# 00C-004.net
KiCad netlist of a schematic drawn in EAGLE
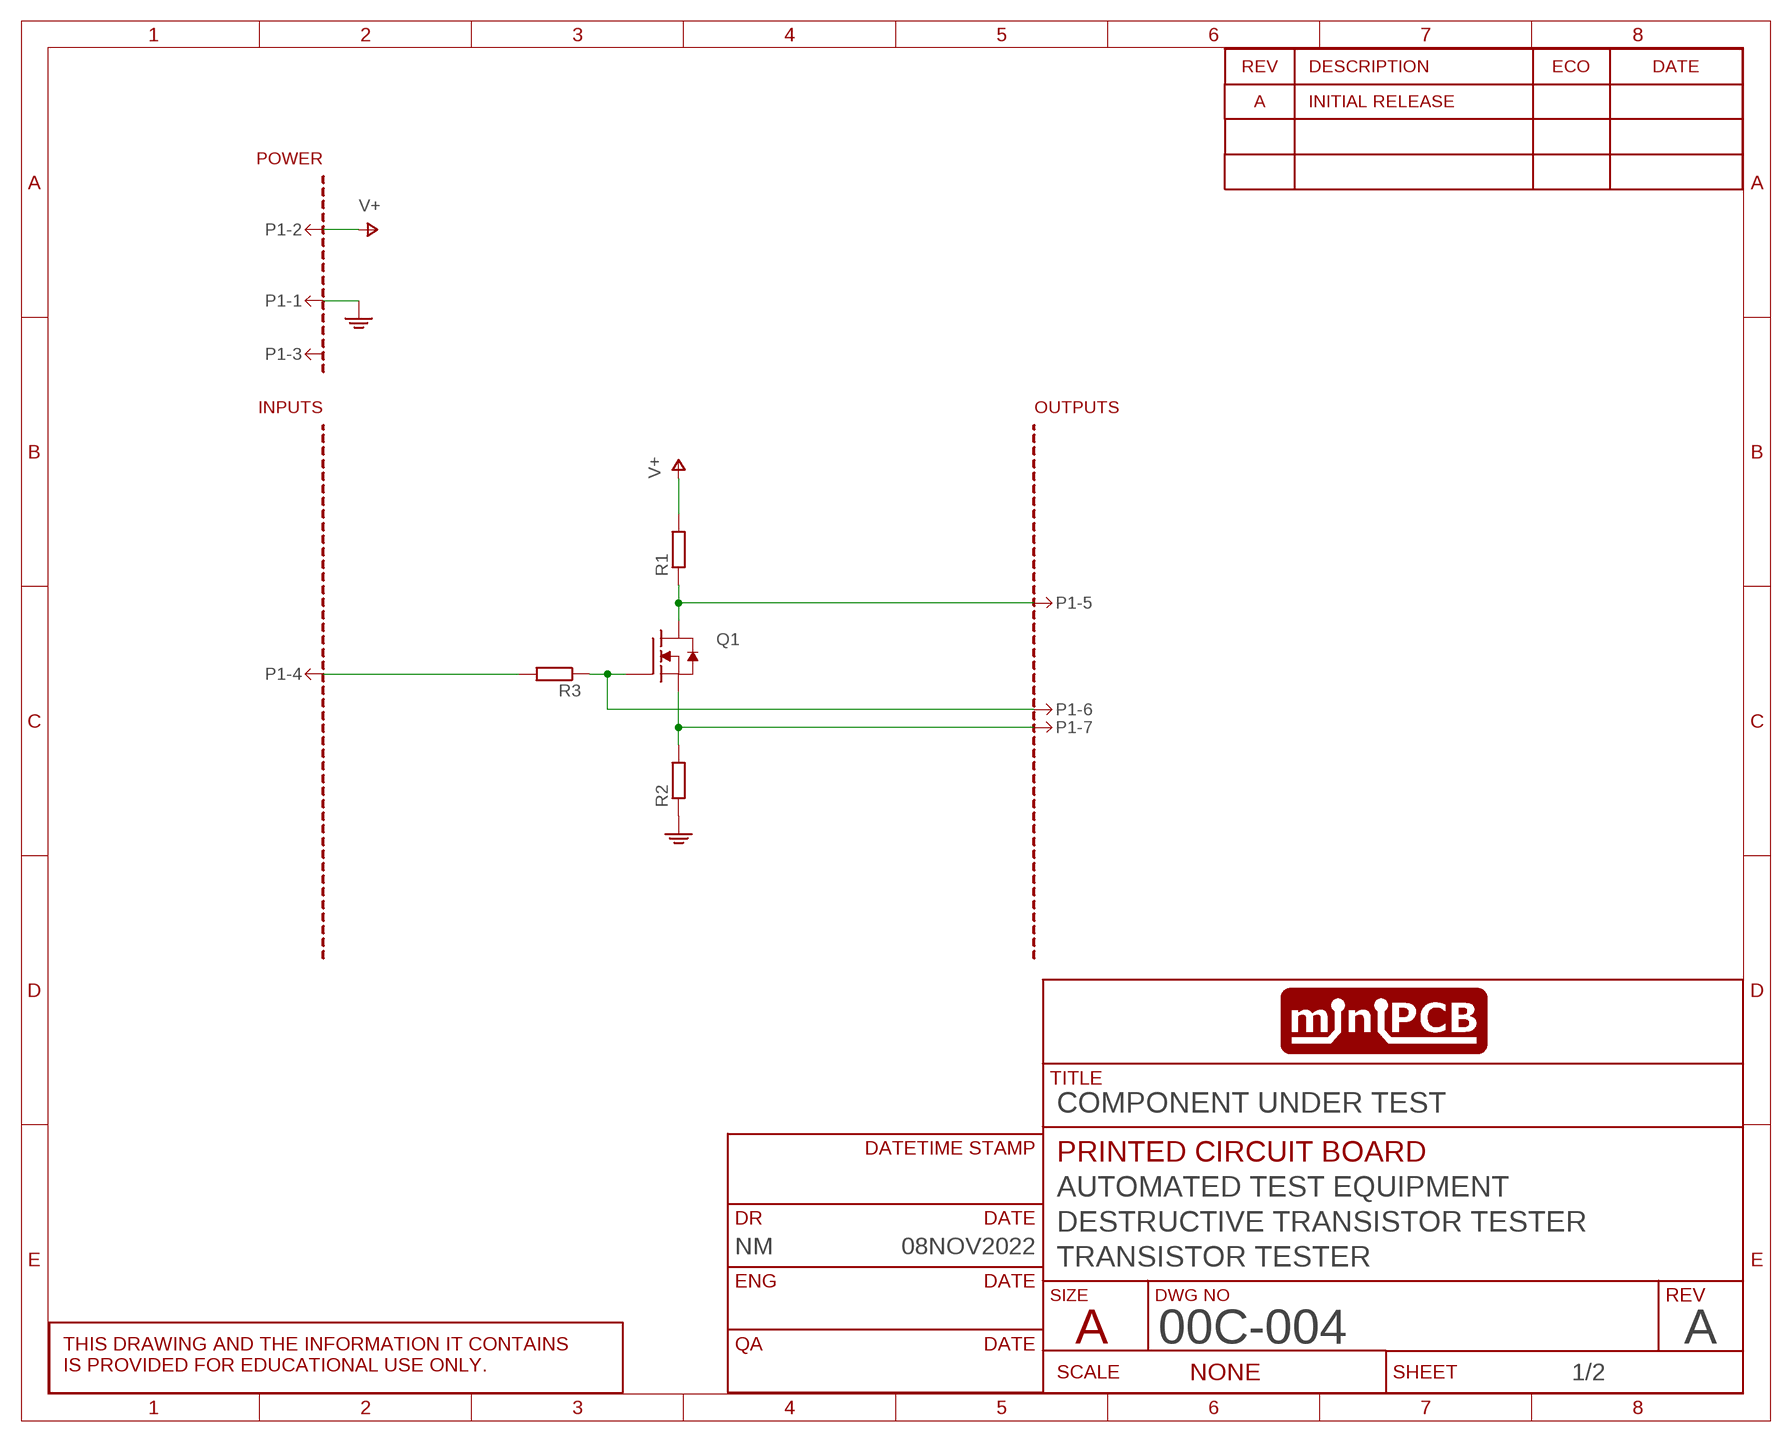
[diagram p0: schematic, sheet 1]
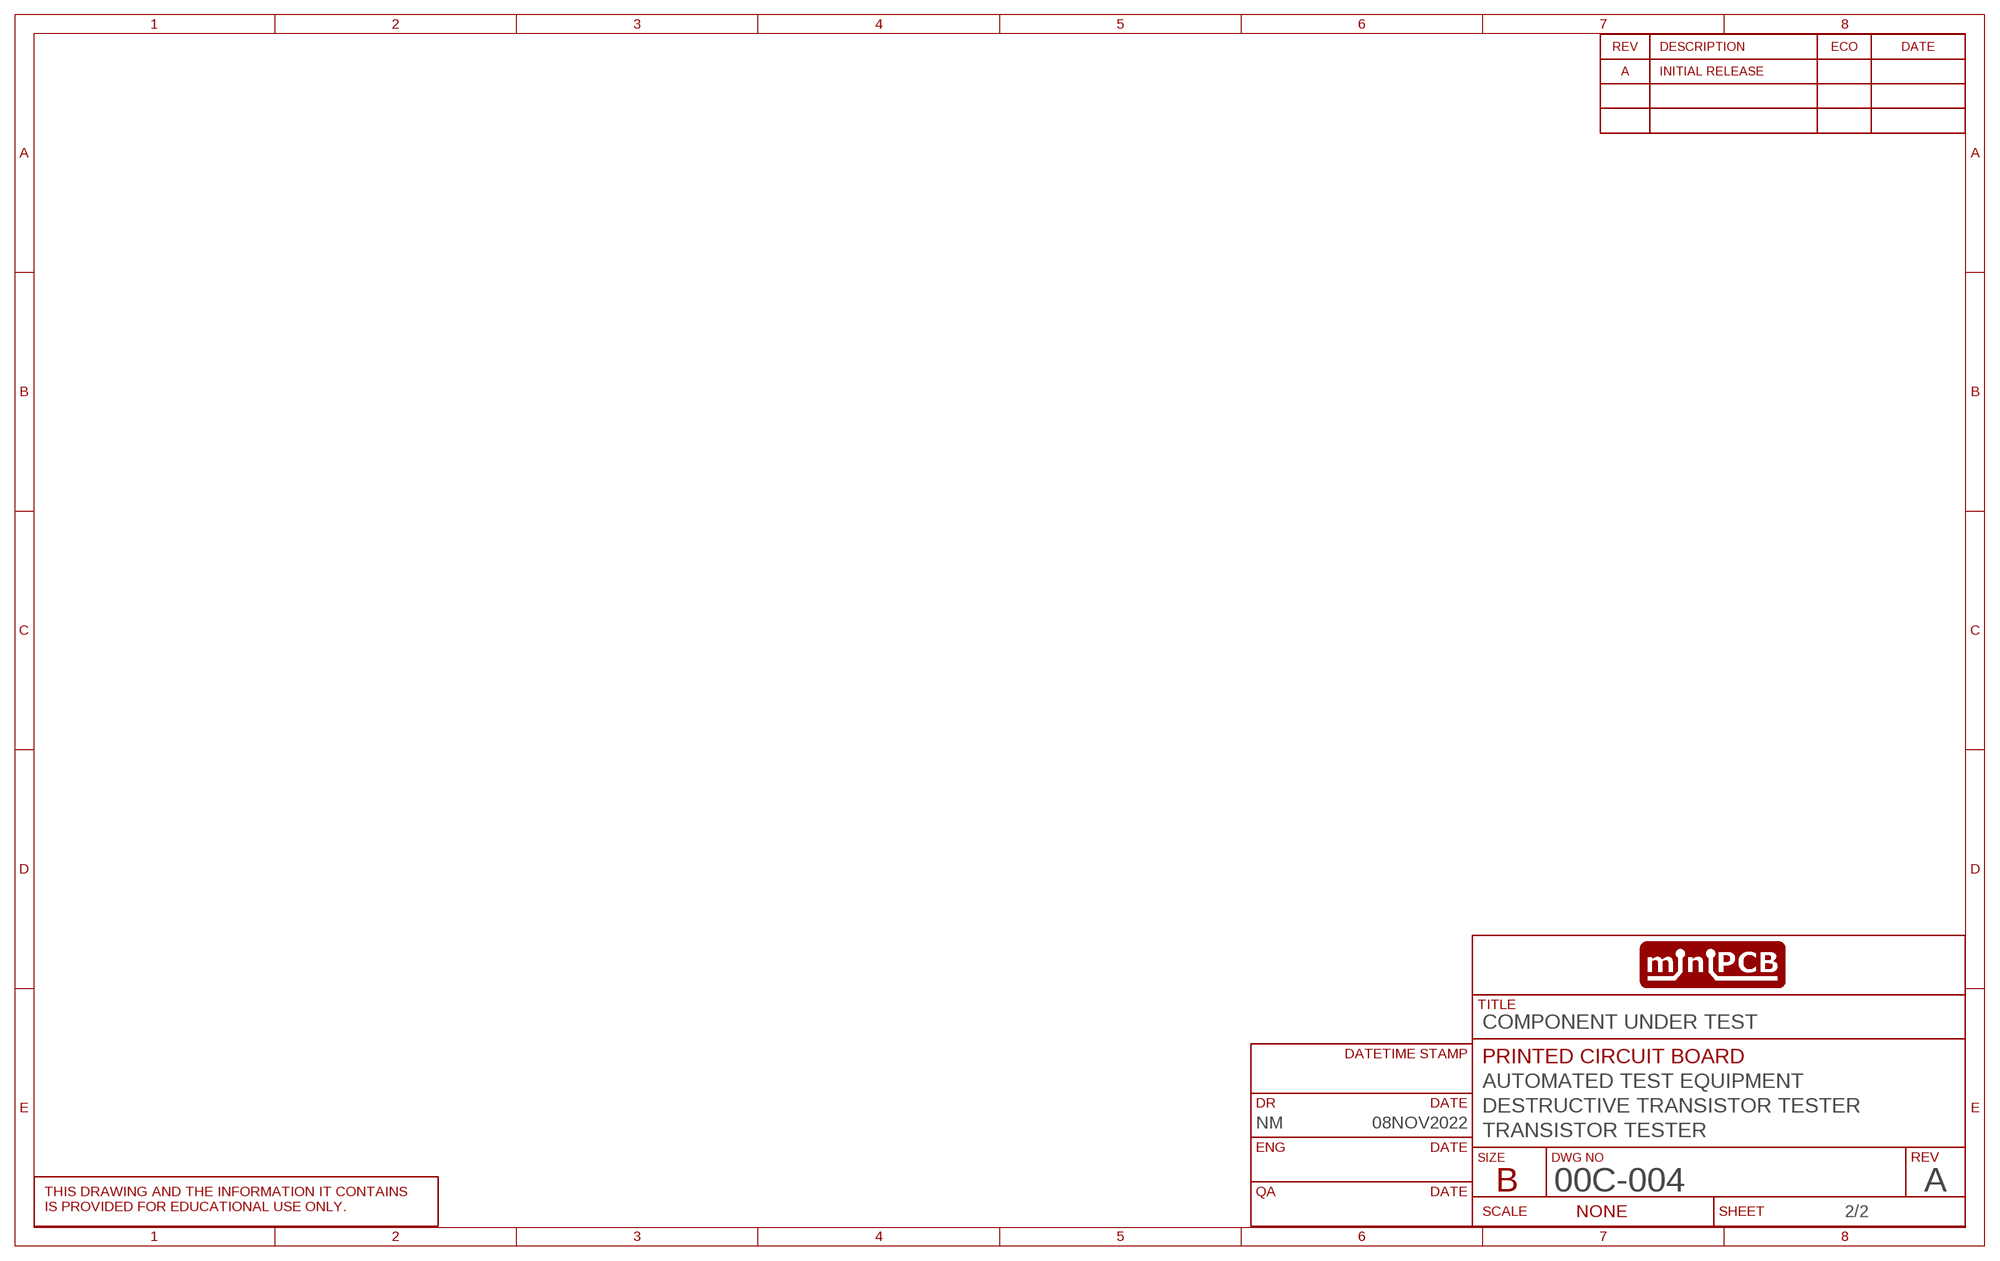
[diagram p1: schematic, sheet 2]

(export (version "E")
  (design (tool "Eeschema 10.0.6"))
  (components
    (comp (ref "P1-")
      (value "MINIPCB_7P50X100")
      (footprint "eagle-import:MINIPCB_7P_50X100")
      (libsource (lib "eagle-import") (part "MINIPCB_7P50X100"))
    )
    (comp (ref "Q1")
      (value "MOSFET-NDPAK")
      (footprint "eagle-import:DPACK")
      (libsource (lib "eagle-import") (part "MOSFET-NDPAK"))
    )
    (comp (ref "R1")
      (value "RESISTORTHD")
      (footprint "eagle-import:0204_7")
      (libsource (lib "eagle-import") (part "RESISTORTHD"))
    )
    (comp (ref "R2")
      (value "RESISTORTHD")
      (footprint "eagle-import:0204_7")
      (libsource (lib "eagle-import") (part "RESISTORTHD"))
    )
    (comp (ref "R3")
      (value "RESISTORTHD")
      (footprint "eagle-import:0204_7")
      (libsource (lib "eagle-import") (part "RESISTORTHD"))
    )
  )
  (nets
    (net (code "1") (name "GND") (class "Default")
      (node (ref "P1-") (pin "1") (pinfunction "1_1") (pintype "bidirectional"))
      (node (ref "R2") (pin "1") (pinfunction "1_1") (pintype "passive"))
    )
    (net (code "2") (name "Net-(P1-D-1)") (class "Default")
      (node (ref "P1-") (pin "4") (pinfunction "1_4") (pintype "bidirectional"))
      (node (ref "R3") (pin "2") (pinfunction "2_2") (pintype "passive"))
    )
    (net (code "3") (name "Net-(P1-E-1)") (class "Default")
      (node (ref "P1-") (pin "5") (pinfunction "1_5") (pintype "bidirectional"))
      (node (ref "Q1") (pin "4") (pinfunction "D_4") (pintype "passive"))
      (node (ref "R1") (pin "1") (pinfunction "1_1") (pintype "passive"))
    )
    (net (code "4") (name "Net-(P1-F-1)") (class "Default")
      (node (ref "P1-") (pin "6") (pinfunction "1_6") (pintype "bidirectional"))
      (node (ref "Q1") (pin "1") (pinfunction "G_1") (pintype "passive"))
      (node (ref "R3") (pin "1") (pinfunction "1_1") (pintype "passive"))
    )
    (net (code "5") (name "Net-(P1-G-1)") (class "Default")
      (node (ref "P1-") (pin "7") (pinfunction "1_7") (pintype "bidirectional"))
      (node (ref "Q1") (pin "3") (pinfunction "S_3") (pintype "passive"))
      (node (ref "R2") (pin "2") (pinfunction "2_2") (pintype "passive"))
    )
    (net (code "6") (name "V+") (class "Default")
      (node (ref "P1-") (pin "2") (pinfunction "1_2") (pintype "bidirectional"))
      (node (ref "R1") (pin "2") (pinfunction "2_2") (pintype "passive"))
    )
    (net (code "7") (name "unconnected-(P1-C-1-Pad3)") (class "Default")
      (node (ref "P1-") (pin "3") (pinfunction "1_3") (pintype "bidirectional"))
    )
  )
)
